# m2_connector.net
KiCad netlist of a schematic drawn in Altium Designer
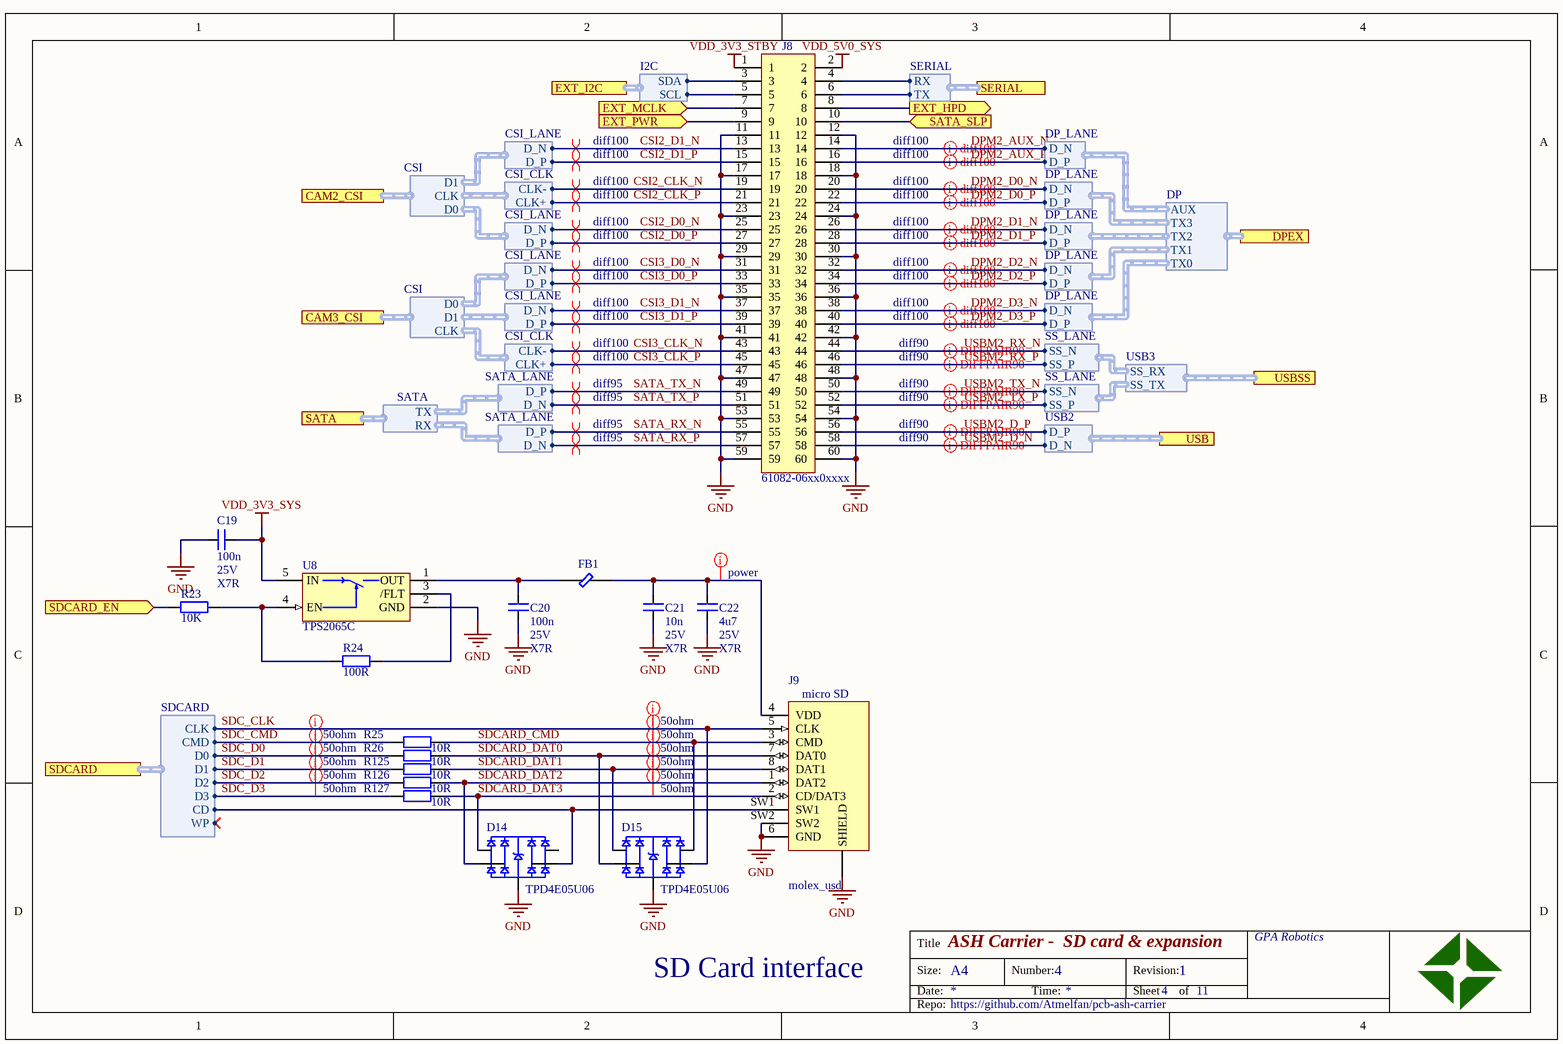
[diagram p0: m2_connector.SchDoc]

(export (version "E")
  (design (tool "Eeschema 10.0.6"))
  (components
    (comp (ref "C19")
      (value "100n")
      (footprint "C1005[0402]")
      (description "Capacitor")
      (fields (field (name "VOLTAGE") "25V") (field (name "TYPE") "X7R") (field (name "Comment") "cap"))
      (libsource (lib "gpa_passives") (part "cap"))
    )
    (comp (ref "C20")
      (value "100n")
      (footprint "C1005[0402]")
      (description "Capacitor")
      (fields (field (name "VOLTAGE") "25V") (field (name "TYPE") "X7R") (field (name "Comment") "cap"))
      (libsource (lib "gpa_passives") (part "cap"))
    )
    (comp (ref "C21")
      (value "10n")
      (footprint "C1005[0402]")
      (description "Capacitor")
      (fields (field (name "VOLTAGE") "25V") (field (name "TYPE") "X7R") (field (name "Comment") "cap"))
      (libsource (lib "gpa_passives") (part "cap"))
    )
    (comp (ref "C22")
      (value "4u7")
      (footprint "C3216[1206]")
      (description "Capacitor")
      (fields (field (name "VOLTAGE") "25V") (field (name "TYPE") "X7R") (field (name "Comment") "cap"))
      (libsource (lib "gpa_passives") (part "cap"))
    )
    (comp (ref "D14")
      (value "TPD4E05U06")
      (footprint "TI_PSON50P100X55-10N")
      (libsource (lib "gpa_ti") (part "tpd4e05u06"))
    )
    (comp (ref "D15")
      (value "TPD4E05U06")
      (footprint "TI_PSON50P100X55-10N")
      (libsource (lib "gpa_ti") (part "tpd4e05u06"))
    )
    (comp (ref "FB1")
      (value "2506036007Y3")
      (footprint "FBC1608X07N")
      (description "Ferrite bead")
      (libsource (lib "gpa_passives") (part "ferrite_bead"))
    )
    (comp (ref "J8")
      (value "61082-06xx0xxxx")
      (footprint "fci_mezzanine_61082")
      (libsource (lib "gpa_connectors") (part "mezzanine_2x30"))
    )
    (comp (ref "J9")
      (value "molex_usd")
      (footprint "molex_usd")
      (libsource (lib "gpa_connectors") (part "molex_usd"))
    )
    (comp (ref "R23")
      (value "10K")
      (footprint "R1005[0402]")
      (description "Resistor")
      (fields (field (name "Comment") "res"))
      (libsource (lib "gpa_passives") (part "res"))
    )
    (comp (ref "R24")
      (value "100R")
      (footprint "R1005[0402]")
      (description "Resistor")
      (fields (field (name "Comment") "res"))
      (libsource (lib "gpa_passives") (part "res"))
    )
    (comp (ref "R25")
      (value "10R")
      (footprint "R1005[0402]")
      (description "Resistor")
      (fields (field (name "Comment") "res"))
      (libsource (lib "gpa_passives") (part "res"))
    )
    (comp (ref "R26")
      (value "10R")
      (footprint "R1005[0402]")
      (description "Resistor")
      (fields (field (name "Comment") "res"))
      (libsource (lib "gpa_passives") (part "res"))
    )
    (comp (ref "R125")
      (value "10R")
      (footprint "R1005[0402]")
      (description "Resistor")
      (fields (field (name "Comment") "res"))
      (libsource (lib "gpa_passives") (part "res"))
    )
    (comp (ref "R126")
      (value "10R")
      (footprint "R1005[0402]")
      (description "Resistor")
      (fields (field (name "Comment") "res"))
      (libsource (lib "gpa_passives") (part "res"))
    )
    (comp (ref "R127")
      (value "10R")
      (footprint "R1005[0402]")
      (description "Resistor")
      (fields (field (name "Comment") "res"))
      (libsource (lib "gpa_passives") (part "res"))
    )
    (comp (ref "U8")
      (value "TPS2065C")
      (footprint "TI_SOT95P280X145-5N")
      (libsource (lib "gpa_ti") (part "tps2065c"))
    )
  )
  (nets
    (net (code "17") (name "/CD") (class "Default")
      (node (ref "D14") (pin "4") (pinfunction "D2-_4") (pintype "passive"))
      (node (ref "J9") (pin "SW1") (pinfunction "SW1_SW1") (pintype "passive"))
    )
    (net (code "18") (name "/CSI2_CLK_N") (class "Default")
      (node (ref "J8") (pin "19") (pinfunction "19_19") (pintype "passive"))
    )
    (net (code "19") (name "/CSI2_CLK_P") (class "Default")
      (node (ref "J8") (pin "21") (pinfunction "21_21") (pintype "passive"))
    )
    (net (code "20") (name "/CSI2_D0_N") (class "Default")
      (node (ref "J8") (pin "25") (pinfunction "25_25") (pintype "passive"))
    )
    (net (code "21") (name "/CSI2_D0_P") (class "Default")
      (node (ref "J8") (pin "27") (pinfunction "27_27") (pintype "passive"))
    )
    (net (code "22") (name "/CSI2_D1_N") (class "Default")
      (node (ref "J8") (pin "13") (pinfunction "13_13") (pintype "passive"))
    )
    (net (code "23") (name "/CSI2_D1_P") (class "Default")
      (node (ref "J8") (pin "15") (pinfunction "15_15") (pintype "passive"))
    )
    (net (code "24") (name "/CSI3_CLK_N") (class "Default")
      (node (ref "J8") (pin "43") (pinfunction "43_43") (pintype "passive"))
    )
    (net (code "25") (name "/CSI3_CLK_P") (class "Default")
      (node (ref "J8") (pin "45") (pinfunction "45_45") (pintype "passive"))
    )
    (net (code "26") (name "/CSI3_D0_N") (class "Default")
      (node (ref "J8") (pin "31") (pinfunction "31_31") (pintype "passive"))
    )
    (net (code "27") (name "/CSI3_D0_P") (class "Default")
      (node (ref "J8") (pin "33") (pinfunction "33_33") (pintype "passive"))
    )
    (net (code "28") (name "/CSI3_D1_N") (class "Default")
      (node (ref "J8") (pin "37") (pinfunction "37_37") (pintype "passive"))
    )
    (net (code "29") (name "/CSI3_D1_P") (class "Default")
      (node (ref "J8") (pin "39") (pinfunction "39_39") (pintype "passive"))
    )
    (net (code "31") (name "/DPM2_AUX_N") (class "Default")
      (node (ref "J8") (pin "14") (pinfunction "14_14") (pintype "passive"))
    )
    (net (code "32") (name "/DPM2_AUX_P") (class "Default")
      (node (ref "J8") (pin "16") (pinfunction "16_16") (pintype "passive"))
    )
    (net (code "33") (name "/DPM2_D0_N") (class "Default")
      (node (ref "J8") (pin "20") (pinfunction "20_20") (pintype "passive"))
    )
    (net (code "34") (name "/DPM2_D0_P") (class "Default")
      (node (ref "J8") (pin "22") (pinfunction "22_22") (pintype "passive"))
    )
    (net (code "35") (name "/DPM2_D1_N") (class "Default")
      (node (ref "J8") (pin "26") (pinfunction "26_26") (pintype "passive"))
    )
    (net (code "36") (name "/DPM2_D1_P") (class "Default")
      (node (ref "J8") (pin "28") (pinfunction "28_28") (pintype "passive"))
    )
    (net (code "37") (name "/DPM2_D2_N") (class "Default")
      (node (ref "J8") (pin "32") (pinfunction "32_32") (pintype "passive"))
    )
    (net (code "38") (name "/DPM2_D2_P") (class "Default")
      (node (ref "J8") (pin "34") (pinfunction "34_34") (pintype "passive"))
    )
    (net (code "39") (name "/DPM2_D3_N") (class "Default")
      (node (ref "J8") (pin "38") (pinfunction "38_38") (pintype "passive"))
    )
    (net (code "40") (name "/DPM2_D3_P") (class "Default")
      (node (ref "J8") (pin "40") (pinfunction "40_40") (pintype "passive"))
    )
    (net (code "41") (name "/EXT_HPD") (class "Default")
      (node (ref "J8") (pin "8") (pinfunction "8_8") (pintype "passive"))
    )
    (net (code "42") (name "/EXT_MCLK") (class "Default")
      (node (ref "J8") (pin "7") (pinfunction "7_7") (pintype "passive"))
    )
    (net (code "43") (name "/EXT_PWR") (class "Default")
      (node (ref "J8") (pin "9") (pinfunction "9_9") (pintype "passive"))
    )
    (net (code "44") (name "/SATA_RX_N") (class "Default")
      (node (ref "J8") (pin "55") (pinfunction "55_55") (pintype "passive"))
    )
    (net (code "45") (name "/SATA_RX_P") (class "Default")
      (node (ref "J8") (pin "57") (pinfunction "57_57") (pintype "passive"))
    )
    (net (code "46") (name "/SATA_SLP") (class "Default")
      (node (ref "J8") (pin "10") (pinfunction "10_10") (pintype "passive"))
    )
    (net (code "47") (name "/SATA_TX_N") (class "Default")
      (node (ref "J8") (pin "49") (pinfunction "49_49") (pintype "passive"))
    )
    (net (code "48") (name "/SATA_TX_P") (class "Default")
      (node (ref "J8") (pin "51") (pinfunction "51_51") (pintype "passive"))
    )
    (net (code "50") (name "/SCL") (class "Default")
      (node (ref "J8") (pin "5") (pinfunction "5_5") (pintype "passive"))
    )
    (net (code "51") (name "/SDA") (class "Default")
      (node (ref "J8") (pin "3") (pinfunction "3_3") (pintype "passive"))
    )
    (net (code "52") (name "/SDCARD_CMD") (class "Default")
      (node (ref "D15") (pin "5") (pinfunction "D2+_5") (pintype "passive"))
      (node (ref "J9") (pin "3") (pinfunction "CMD_3") (pintype "bidirectional"))
      (node (ref "R25") (pin "2") (pinfunction "2_2") (pintype "passive"))
    )
    (net (code "53") (name "/SDCARD_DAT0") (class "Default")
      (node (ref "D15") (pin "2") (pinfunction "D1-_2") (pintype "passive"))
      (node (ref "J9") (pin "7") (pinfunction "DAT0_7") (pintype "bidirectional"))
      (node (ref "R26") (pin "2") (pinfunction "2_2") (pintype "passive"))
    )
    (net (code "54") (name "/SDCARD_DAT1") (class "Default")
      (node (ref "D15") (pin "1") (pinfunction "D1+_1") (pintype "passive"))
      (node (ref "J9") (pin "8") (pinfunction "DAT1_8") (pintype "bidirectional"))
      (node (ref "R125") (pin "2") (pinfunction "2_2") (pintype "passive"))
    )
    (net (code "55") (name "/SDCARD_DAT2") (class "Default")
      (node (ref "D14") (pin "2") (pinfunction "D1-_2") (pintype "passive"))
      (node (ref "J9") (pin "1") (pinfunction "DAT2_1") (pintype "bidirectional"))
      (node (ref "R126") (pin "2") (pinfunction "2_2") (pintype "passive"))
    )
    (net (code "56") (name "/SDCARD_DAT3") (class "Default")
      (node (ref "D14") (pin "1") (pinfunction "D1+_1") (pintype "passive"))
      (node (ref "J9") (pin "2") (pinfunction "CD/DAT3_2") (pintype "bidirectional"))
      (node (ref "R127") (pin "2") (pinfunction "2_2") (pintype "passive"))
    )
    (net (code "57") (name "/SDCARD_EN") (class "Default")
      (node (ref "R23") (pin "1") (pinfunction "1_1") (pintype "passive"))
    )
    (net (code "58") (name "/SDC_CLK") (class "Default")
      (node (ref "D15") (pin "4") (pinfunction "D2-_4") (pintype "passive"))
      (node (ref "J9") (pin "5") (pinfunction "CLK_5") (pintype "input"))
    )
    (net (code "59") (name "/SDC_CMD") (class "Default")
      (node (ref "R25") (pin "1") (pinfunction "1_1") (pintype "passive"))
    )
    (net (code "60") (name "/SDC_D0") (class "Default")
      (node (ref "R26") (pin "1") (pinfunction "1_1") (pintype "passive"))
    )
    (net (code "61") (name "/SDC_D1") (class "Default")
      (node (ref "R125") (pin "1") (pinfunction "1_1") (pintype "passive"))
    )
    (net (code "62") (name "/SDC_D2") (class "Default")
      (node (ref "R126") (pin "1") (pinfunction "1_1") (pintype "passive"))
    )
    (net (code "63") (name "/SDC_D3") (class "Default")
      (node (ref "R127") (pin "1") (pinfunction "1_1") (pintype "passive"))
    )
    (net (code "64") (name "/USBM2_D_N") (class "Default")
      (node (ref "J8") (pin "58") (pinfunction "58_58") (pintype "passive"))
    )
    (net (code "65") (name "/USBM2_D_P") (class "Default")
      (node (ref "J8") (pin "56") (pinfunction "56_56") (pintype "passive"))
    )
    (net (code "66") (name "/USBM2_RX_N") (class "Default")
      (node (ref "J8") (pin "44") (pinfunction "44_44") (pintype "passive"))
    )
    (net (code "67") (name "/USBM2_RX_P") (class "Default")
      (node (ref "J8") (pin "46") (pinfunction "46_46") (pintype "passive"))
    )
    (net (code "68") (name "/USBM2_TX_N") (class "Default")
      (node (ref "J8") (pin "50") (pinfunction "50_50") (pintype "passive"))
    )
    (net (code "69") (name "/USBM2_TX_P") (class "Default")
      (node (ref "J8") (pin "52") (pinfunction "52_52") (pintype "passive"))
    )
    (net (code "80") (name "GND") (class "Default")
      (node (ref "C19") (pin "2") (pinfunction "2_2") (pintype "passive"))
      (node (ref "C20") (pin "1") (pinfunction "1_1") (pintype "passive"))
      (node (ref "C21") (pin "1") (pinfunction "1_1") (pintype "passive"))
      (node (ref "C22") (pin "1") (pinfunction "1_1") (pintype "passive"))
      (node (ref "D14") (pin "3") (pinfunction "GND_3") (pintype "passive"))
      (node (ref "D15") (pin "3") (pinfunction "GND_3") (pintype "passive"))
      (node (ref "J8") (pin "11") (pinfunction "11_11") (pintype "passive"))
      (node (ref "J8") (pin "12") (pinfunction "12_12") (pintype "passive"))
      (node (ref "J8") (pin "17") (pinfunction "17_17") (pintype "passive"))
      (node (ref "J8") (pin "18") (pinfunction "18_18") (pintype "passive"))
      (node (ref "J8") (pin "23") (pinfunction "23_23") (pintype "passive"))
      (node (ref "J8") (pin "24") (pinfunction "24_24") (pintype "passive"))
      (node (ref "J8") (pin "29") (pinfunction "29_29") (pintype "passive"))
      (node (ref "J8") (pin "30") (pinfunction "30_30") (pintype "passive"))
      (node (ref "J8") (pin "35") (pinfunction "35_35") (pintype "passive"))
      (node (ref "J8") (pin "36") (pinfunction "36_36") (pintype "passive"))
      (node (ref "J8") (pin "41") (pinfunction "41_41") (pintype "passive"))
      (node (ref "J8") (pin "42") (pinfunction "42_42") (pintype "passive"))
      (node (ref "J8") (pin "47") (pinfunction "47_47") (pintype "passive"))
      (node (ref "J8") (pin "48") (pinfunction "48_48") (pintype "passive"))
      (node (ref "J8") (pin "53") (pinfunction "53_53") (pintype "passive"))
      (node (ref "J8") (pin "54") (pinfunction "54_54") (pintype "passive"))
      (node (ref "J8") (pin "59") (pinfunction "59_59") (pintype "passive"))
      (node (ref "J8") (pin "60") (pinfunction "60_60") (pintype "passive"))
      (node (ref "J9") (pin "6") (pinfunction "GND_6") (pintype "power_in"))
      (node (ref "J9") (pin "SHIELD") (pinfunction "SHIELD_SHIELD") (pintype "passive"))
      (node (ref "J9") (pin "SW2") (pinfunction "SW2_SW2") (pintype "passive"))
      (node (ref "U8") (pin "2") (pinfunction "GND_2") (pintype "power_in"))
    )
    (net (code "81") (name "Net-(J9-VDD)") (class "Default")
      (node (ref "C21") (pin "2") (pinfunction "2_2") (pintype "passive"))
      (node (ref "C22") (pin "2") (pinfunction "2_2") (pintype "passive"))
      (node (ref "FB1") (pin "2") (pinfunction "2_2") (pintype "passive"))
      (node (ref "J9") (pin "4") (pinfunction "VDD_4") (pintype "power_in"))
    )
    (net (code "82") (name "Net-(U8-EN)") (class "Default")
      (node (ref "R23") (pin "2") (pinfunction "2_2") (pintype "passive"))
      (node (ref "R24") (pin "1") (pinfunction "1_1") (pintype "passive"))
      (node (ref "U8") (pin "4") (pinfunction "EN_4") (pintype "input"))
    )
    (net (code "83") (name "Net-(U8-OUT)") (class "Default")
      (node (ref "C20") (pin "2") (pinfunction "2_2") (pintype "passive"))
      (node (ref "FB1") (pin "1") (pinfunction "1_1") (pintype "passive"))
      (node (ref "U8") (pin "1") (pinfunction "OUT_1") (pintype "power_in"))
    )
    (net (code "84") (name "Net-(U8-{slash}FLT)") (class "Default")
      (node (ref "R24") (pin "2") (pinfunction "2_2") (pintype "passive"))
      (node (ref "U8") (pin "3") (pinfunction "/FLT_3") (pintype "open_collector"))
    )
    (net (code "85") (name "VDD_3V3_STBY") (class "Default")
      (node (ref "J8") (pin "1") (pinfunction "1_1") (pintype "passive"))
    )
    (net (code "86") (name "VDD_3V3_SYS") (class "Default")
      (node (ref "C19") (pin "1") (pinfunction "1_1") (pintype "passive"))
      (node (ref "U8") (pin "5") (pinfunction "IN_5") (pintype "power_in"))
    )
    (net (code "87") (name "VDD_5V0_SYS") (class "Default")
      (node (ref "J8") (pin "2") (pinfunction "2_2") (pintype "passive"))
    )
    (net (code "88") (name "unconnected-(D14-D2+-Pad5)") (class "Default")
      (node (ref "D14") (pin "5") (pinfunction "D2+_5") (pintype "passive"))
    )
    (net (code "89") (name "unconnected-(J8-Pad4)") (class "Default")
      (node (ref "J8") (pin "4") (pinfunction "4_4") (pintype "passive"))
    )
    (net (code "90") (name "unconnected-(J8-Pad6)") (class "Default")
      (node (ref "J8") (pin "6") (pinfunction "6_6") (pintype "passive"))
    )
  )
)
